# Raspberry_Pi_Interface.net
KiCad netlist of a schematic drawn in Altium Designer
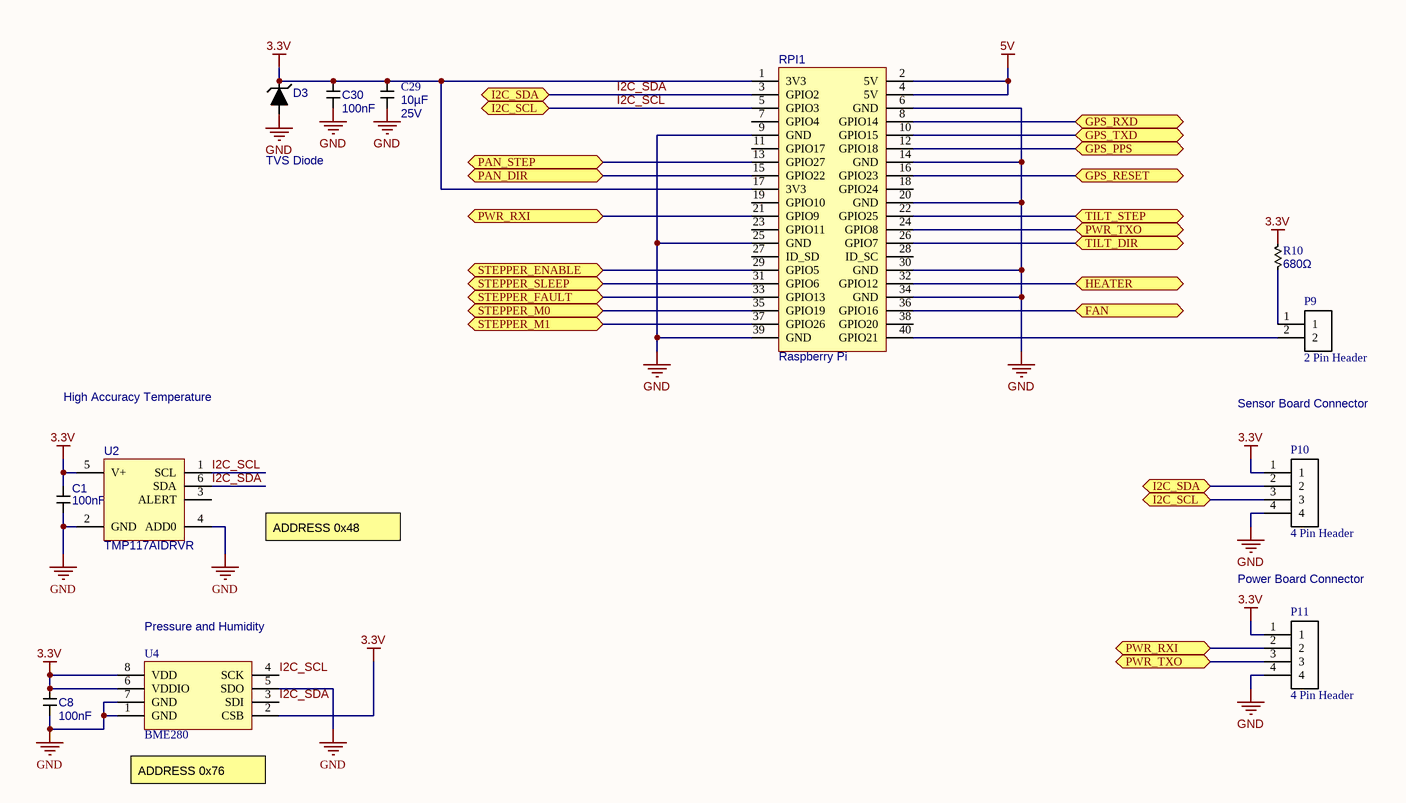
[diagram p0: Raspberry Pi Interface.SchDoc]

(export (version "E")
  (design (tool "Eeschema 10.0.6"))
  (components
    (comp (ref "C1")
      (value "100nF")
      (footprint "C0805")
      (description "Capacitor")
      (fields
        (field (name "MANUFACTURER") "YAGEO")
        (field (name "MANUFACTURER PART NUMBER") "CC0805KRX7R9BB104")
      )
      (libsource (lib "Rigby Electronics Schematic Library") (part "Capacitor"))
    )
    (comp (ref "C8")
      (value "100nF")
      (footprint "C0805")
      (description "Capacitor")
      (fields
        (field (name "MANUFACTURER") "YAGEO")
        (field (name "MANUFACTURER PART NUMBER") "CC0805KRX7R9BB104")
      )
      (libsource (lib "Rigby Electronics Schematic Library") (part "Capacitor"))
    )
    (comp (ref "C29")
      (value "F")
      (footprint "C0805")
      (description "Capacitor")
      (fields
        (field (name "MANUFACTURER") "Samsung Electro-Mechanics")
        (field (name "MANUFACTURER PART NUMBER") "CL21A106KAYNNNG")
        (field (name "VOLTAGE RATING") "25V")
        (field (name "CAPACITANCE") "10µF")
      )
      (libsource (lib "Rigby Electronics Schematic Library") (part "Capacitor"))
    )
    (comp (ref "C30")
      (value "100nF")
      (footprint "C0805")
      (description "Capacitor")
      (fields
        (field (name "MANUFACTURER") "YAGEO")
        (field (name "MANUFACTURER PART NUMBER") "CC0805KRX7R9BB104")
      )
      (libsource (lib "Rigby Electronics Schematic Library") (part "Capacitor"))
    )
    (comp (ref "D3")
      (value "TVS Diode")
      (footprint "SP4020-01FTG-C")
      (fields
        (field (name "MANUFACTURER") "Littelfuse Inc.")
        (field (name "MANUFACTURER PART NUMBER") "SP4020-01FTG-C")
      )
      (libsource (lib "Rigby Electronics Schematic Library") (part "Diode TVS"))
    )
    (comp (ref "P9")
      (value "2 Pin Header")
      (footprint "S2B-XH-A(LF)(SN)")
      (fields
        (field (name "MANUFACTURER") "JST Sales America Inc.")
        (field (name "MANUFACTURER PART NUMBER") "S2B-XH-A")
      )
      (libsource (lib "Rigby Electronics Schematic Library") (part "Header 2"))
    )
    (comp (ref "P10")
      (value "4 Pin Header")
      (footprint "B4B-XH-A")
      (fields (field (name "MANUFACTURER") "JST") (field (name "MANUFACTURER PART NUMBER") "B4B-XH-2"))
      (libsource (lib "Rigby Electronics Schematic Library") (part "Header 4"))
    )
    (comp (ref "P11")
      (value "4 Pin Header")
      (footprint "B4B-XH-A")
      (fields (field (name "MANUFACTURER") "JST") (field (name "MANUFACTURER PART NUMBER") "B4B-XH-2"))
      (libsource (lib "Rigby Electronics Schematic Library") (part "Header 4"))
    )
    (comp (ref "R10")
      (value "680Ω")
      (footprint "R0805")
      (description "Standard Resistor")
      (fields
        (field (name "MANUFACTURER") "Panasonic Electronic Components")
        (field (name "MANUFACTURER PART NUMBER") "ERJ-6GEYJ681V")
        (field (name "RESISTANCE") "680Ω")
      )
      (libsource (lib "Rigby Electronics Schematic Library") (part "Resistor"))
    )
    (comp (ref "RPI1")
      (value "Raspberry Pi")
      (footprint "Raspberry Pi 4B")
      (description "Raspberry Pi 40 Pin Header")
      (fields
        (field (name "MANUFACTURER PART NUMBER") "PPTC202LFBN-RC")
        (field (name "MANUFACTURER") "Sullins Connector Solutions")
      )
      (libsource (lib "Rigby Electronics Schematic Library") (part "Raspberry Pi 40 Pin Header"))
    )
    (comp (ref "U2")
      (value "TMP117AIDRVR")
      (footprint "TMP117AIDRVR")
      (description "Temperature Sensor Digital, Local -55°C ~ 150°C 16 b 6-WSON (2x2)")
      (fields (field (name "MANUFACTURER") "Texas Instruments"))
      (libsource (lib "Rigby Electronics Schematic Library") (part "TMP117AIDRVR"))
    )
    (comp (ref "U4")
      (value "BME280")
      (footprint "BME280")
      (description "Pressure and Humidity Sensor")
      (fields (field (name "MANUFACTURER") "Bosch Sensortec"))
      (libsource (lib "Rigby Electronics Schematic Library") (part "BME280"))
    )
  )
  (nets
    (net (code "1") (name "/FAN") (class "Default")
      (node (ref "RPI1") (pin "36") (pinfunction "GPIO16_36") (pintype "passive"))
    )
    (net (code "2") (name "/GPS_PPS") (class "Default")
      (node (ref "RPI1") (pin "12") (pinfunction "GPIO18_12") (pintype "passive"))
    )
    (net (code "3") (name "/GPS_RESET") (class "Default")
      (node (ref "RPI1") (pin "16") (pinfunction "GPIO23_16") (pintype "passive"))
    )
    (net (code "4") (name "/GPS_RXD") (class "Default")
      (node (ref "RPI1") (pin "8") (pinfunction "GPIO14_8") (pintype "passive"))
    )
    (net (code "5") (name "/GPS_TXD") (class "Default")
      (node (ref "RPI1") (pin "10") (pinfunction "GPIO15_10") (pintype "passive"))
    )
    (net (code "6") (name "/HEATER") (class "Default")
      (node (ref "RPI1") (pin "32") (pinfunction "GPIO12_32") (pintype "passive"))
    )
    (net (code "7") (name "/I2C_SCL") (class "Default")
      (node (ref "P10") (pin "3") (pinfunction "3_3") (pintype "passive"))
      (node (ref "RPI1") (pin "5") (pinfunction "GPIO3_5") (pintype "passive"))
      (node (ref "U2") (pin "1") (pinfunction "SCL_1") (pintype "passive"))
      (node (ref "U4") (pin "4") (pinfunction "SCK_4") (pintype "passive"))
    )
    (net (code "8") (name "/I2C_SDA") (class "Default")
      (node (ref "P10") (pin "2") (pinfunction "2_2") (pintype "passive"))
      (node (ref "RPI1") (pin "3") (pinfunction "GPIO2_3") (pintype "passive"))
      (node (ref "U2") (pin "6") (pinfunction "SDA_6") (pintype "passive"))
      (node (ref "U4") (pin "3") (pinfunction "SDI_3") (pintype "passive"))
    )
    (net (code "9") (name "/PAN_DIR") (class "Default")
      (node (ref "RPI1") (pin "15") (pinfunction "GPIO22_15") (pintype "passive"))
    )
    (net (code "10") (name "/PAN_STEP") (class "Default")
      (node (ref "RPI1") (pin "13") (pinfunction "GPIO27_13") (pintype "passive"))
    )
    (net (code "11") (name "/PWR_RXI") (class "Default")
      (node (ref "P11") (pin "2") (pinfunction "2_2") (pintype "passive"))
      (node (ref "RPI1") (pin "21") (pinfunction "GPIO9_21") (pintype "passive"))
    )
    (net (code "12") (name "/PWR_TXO") (class "Default")
      (node (ref "P11") (pin "3") (pinfunction "3_3") (pintype "passive"))
      (node (ref "RPI1") (pin "24") (pinfunction "GPIO8_24") (pintype "passive"))
    )
    (net (code "13") (name "/STEPPER_ENABLE") (class "Default")
      (node (ref "RPI1") (pin "29") (pinfunction "GPIO5_29") (pintype "passive"))
    )
    (net (code "14") (name "/STEPPER_FAULT") (class "Default")
      (node (ref "RPI1") (pin "33") (pinfunction "GPIO13_33") (pintype "passive"))
    )
    (net (code "15") (name "/STEPPER_M0") (class "Default")
      (node (ref "RPI1") (pin "35") (pinfunction "GPIO19_35") (pintype "passive"))
    )
    (net (code "16") (name "/STEPPER_M1") (class "Default")
      (node (ref "RPI1") (pin "37") (pinfunction "GPIO26_37") (pintype "passive"))
    )
    (net (code "17") (name "/STEPPER_SLEEP") (class "Default")
      (node (ref "RPI1") (pin "31") (pinfunction "GPIO6_31") (pintype "passive"))
    )
    (net (code "18") (name "/TILT_DIR") (class "Default")
      (node (ref "RPI1") (pin "26") (pinfunction "GPIO7_26") (pintype "passive"))
    )
    (net (code "19") (name "/TILT_STEP") (class "Default")
      (node (ref "RPI1") (pin "22") (pinfunction "GPIO25_22") (pintype "passive"))
    )
    (net (code "20") (name "3.3V") (class "Default")
      (node (ref "C1") (pin "1") (pinfunction "1_1") (pintype "passive"))
      (node (ref "C29") (pin "1") (pinfunction "1_1") (pintype "passive"))
      (node (ref "C30") (pin "1") (pinfunction "1_1") (pintype "passive"))
      (node (ref "C8") (pin "1") (pinfunction "1_1") (pintype "passive"))
      (node (ref "D3") (pin "1") (pinfunction "1_1") (pintype "passive"))
      (node (ref "P10") (pin "1") (pinfunction "1_1") (pintype "passive"))
      (node (ref "P11") (pin "1") (pinfunction "1_1") (pintype "passive"))
      (node (ref "R10") (pin "2") (pinfunction "2_2") (pintype "passive"))
      (node (ref "RPI1") (pin "1") (pinfunction "3V3_1") (pintype "passive"))
      (node (ref "RPI1") (pin "17") (pinfunction "3V3_17") (pintype "passive"))
      (node (ref "U2") (pin "5") (pinfunction "V+_5") (pintype "passive"))
      (node (ref "U4") (pin "2") (pinfunction "CSB_2") (pintype "passive"))
      (node (ref "U4") (pin "6") (pinfunction "VDDIO_6") (pintype "passive"))
      (node (ref "U4") (pin "8") (pinfunction "VDD_8") (pintype "passive"))
    )
    (net (code "21") (name "5V") (class "Default")
      (node (ref "RPI1") (pin "2") (pinfunction "5V_2") (pintype "passive"))
      (node (ref "RPI1") (pin "4") (pinfunction "5V_4") (pintype "passive"))
    )
    (net (code "22") (name "GND") (class "Default")
      (node (ref "C1") (pin "2") (pinfunction "2_2") (pintype "passive"))
      (node (ref "C29") (pin "2") (pinfunction "2_2") (pintype "passive"))
      (node (ref "C30") (pin "2") (pinfunction "2_2") (pintype "passive"))
      (node (ref "C8") (pin "2") (pinfunction "2_2") (pintype "passive"))
      (node (ref "D3") (pin "2") (pinfunction "2_2") (pintype "passive"))
      (node (ref "P10") (pin "4") (pinfunction "4_4") (pintype "passive"))
      (node (ref "P11") (pin "4") (pinfunction "4_4") (pintype "passive"))
      (node (ref "RPI1") (pin "14") (pinfunction "GND_14") (pintype "passive"))
      (node (ref "RPI1") (pin "20") (pinfunction "GND_20") (pintype "passive"))
      (node (ref "RPI1") (pin "25") (pinfunction "GND_25") (pintype "passive"))
      (node (ref "RPI1") (pin "30") (pinfunction "GND_30") (pintype "passive"))
      (node (ref "RPI1") (pin "34") (pinfunction "GND_34") (pintype "passive"))
      (node (ref "RPI1") (pin "39") (pinfunction "GND_39") (pintype "passive"))
      (node (ref "RPI1") (pin "6") (pinfunction "GND_6") (pintype "passive"))
      (node (ref "RPI1") (pin "9") (pinfunction "GND_9") (pintype "passive"))
      (node (ref "U2") (pin "2") (pinfunction "GND_2") (pintype "passive"))
      (node (ref "U2") (pin "4") (pinfunction "ADD0_4") (pintype "passive"))
      (node (ref "U4") (pin "1") (pinfunction "GND_1") (pintype "passive"))
      (node (ref "U4") (pin "5") (pinfunction "SDO_5") (pintype "passive"))
      (node (ref "U4") (pin "7") (pinfunction "GND_7") (pintype "passive"))
    )
    (net (code "23") (name "Net-(P9-Pad1)") (class "Default")
      (node (ref "P9") (pin "1") (pinfunction "1_1") (pintype "passive"))
      (node (ref "R10") (pin "1") (pinfunction "1_1") (pintype "passive"))
    )
    (net (code "24") (name "Net-(RPI1-GPIO21)") (class "Default")
      (node (ref "P9") (pin "2") (pinfunction "2_2") (pintype "passive"))
      (node (ref "RPI1") (pin "40") (pinfunction "GPIO21_40") (pintype "passive"))
    )
    (net (code "25") (name "unconnected-(RPI1-GPIO4-Pad7)") (class "Default")
      (node (ref "RPI1") (pin "7") (pinfunction "GPIO4_7") (pintype "passive"))
    )
    (net (code "26") (name "unconnected-(RPI1-GPIO10-Pad19)") (class "Default")
      (node (ref "RPI1") (pin "19") (pinfunction "GPIO10_19") (pintype "passive"))
    )
    (net (code "27") (name "unconnected-(RPI1-GPIO11-Pad23)") (class "Default")
      (node (ref "RPI1") (pin "23") (pinfunction "GPIO11_23") (pintype "passive"))
    )
    (net (code "28") (name "unconnected-(RPI1-GPIO17-Pad11)") (class "Default")
      (node (ref "RPI1") (pin "11") (pinfunction "GPIO17_11") (pintype "passive"))
    )
    (net (code "29") (name "unconnected-(RPI1-GPIO20-Pad38)") (class "Default")
      (node (ref "RPI1") (pin "38") (pinfunction "GPIO20_38") (pintype "passive"))
    )
    (net (code "30") (name "unconnected-(RPI1-GPIO24-Pad18)") (class "Default")
      (node (ref "RPI1") (pin "18") (pinfunction "GPIO24_18") (pintype "passive"))
    )
    (net (code "31") (name "unconnected-(RPI1-ID_SC-Pad28)") (class "Default")
      (node (ref "RPI1") (pin "28") (pinfunction "ID_SC_28") (pintype "passive"))
    )
    (net (code "32") (name "unconnected-(RPI1-ID_SD-Pad27)") (class "Default")
      (node (ref "RPI1") (pin "27") (pinfunction "ID_SD_27") (pintype "passive"))
    )
    (net (code "33") (name "unconnected-(U2-ALERT-Pad3)") (class "Default")
      (node (ref "U2") (pin "3") (pinfunction "ALERT_3") (pintype "passive"))
    )
  )
)
